# regulador.net
KiCad netlist of a schematic drawn in Altium Designer
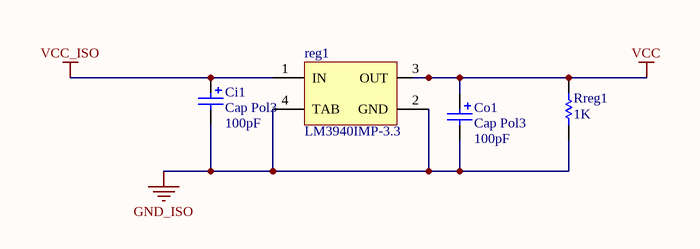
[diagram p0: regulador.SchDoc]

(export (version "E")
  (design (tool "Eeschema 10.0.6"))
  (components
    (comp (ref "Ci1")
      (value "Cap Pol3")
      (footprint "C0805")
      (description "Polarized Capacitor (Surface Mount)")
      (fields (field (name "ALTIUM_VALUE") "100pF") (field (name "PUBLISHER") "Altium Limited"))
      (libsource (lib "Miscellaneous Devices") (part "Cap Pol3"))
    )
    (comp (ref "Co1")
      (value "Cap Pol3")
      (footprint "C0805")
      (description "Polarized Capacitor (Surface Mount)")
      (fields (field (name "ALTIUM_VALUE") "100pF") (field (name "PUBLISHER") "Altium Limited"))
      (libsource (lib "Miscellaneous Devices") (part "Cap Pol3"))
    )
    (comp (ref "reg1")
      (value "LM3940IMP-3.3")
      (footprint "MP04A_N")
      (description "1A Low Dropout Regulator for 5V to 3.3V Conversion, 4-pin SOT-223")
      (fields
        (field (name "MANUFACTURER") "National Semiconductor")
        (field (name "PUBLISHER") "Altium Limited")
      )
      (libsource (lib "NSC LDO") (part "LM3940IMP-3.3"))
    )
    (comp (ref "Rreg1")
      (value "1K")
      (footprint "2012[0805]")
      (description "Semiconductor Resistor")
      (fields (field (name "Comment") "Res Semi") (field (name "PUBLISHER") "Altium Limited"))
      (libsource (lib "Miscellaneous Devices") (part "Res Semi"))
    )
  )
  (nets
    (net (code "1") (name "GND_ISO") (class "Default")
      (node (ref "Ci1") (pin "2") (pinfunction "2_2") (pintype "passive"))
      (node (ref "Co1") (pin "2") (pinfunction "2_2") (pintype "passive"))
      (node (ref "Rreg1") (pin "1") (pinfunction "1_1") (pintype "passive"))
      (node (ref "reg1") (pin "2") (pinfunction "GND_2") (pintype "power_in"))
      (node (ref "reg1") (pin "4") (pinfunction "TAB_4") (pintype "power_in"))
    )
    (net (code "2") (name "VCC") (class "Default")
      (node (ref "Co1") (pin "1") (pinfunction "1_1") (pintype "passive"))
      (node (ref "Rreg1") (pin "2") (pinfunction "2_2") (pintype "passive"))
      (node (ref "reg1") (pin "3") (pinfunction "OUT_3") (pintype "power_in"))
    )
    (net (code "3") (name "VCC_ISO") (class "Default")
      (node (ref "Ci1") (pin "1") (pinfunction "1_1") (pintype "passive"))
      (node (ref "reg1") (pin "1") (pinfunction "IN_1") (pintype "power_in"))
    )
  )
)
